# APP_1_Power_m.net
KiCad netlist of a schematic drawn in Altium Designer
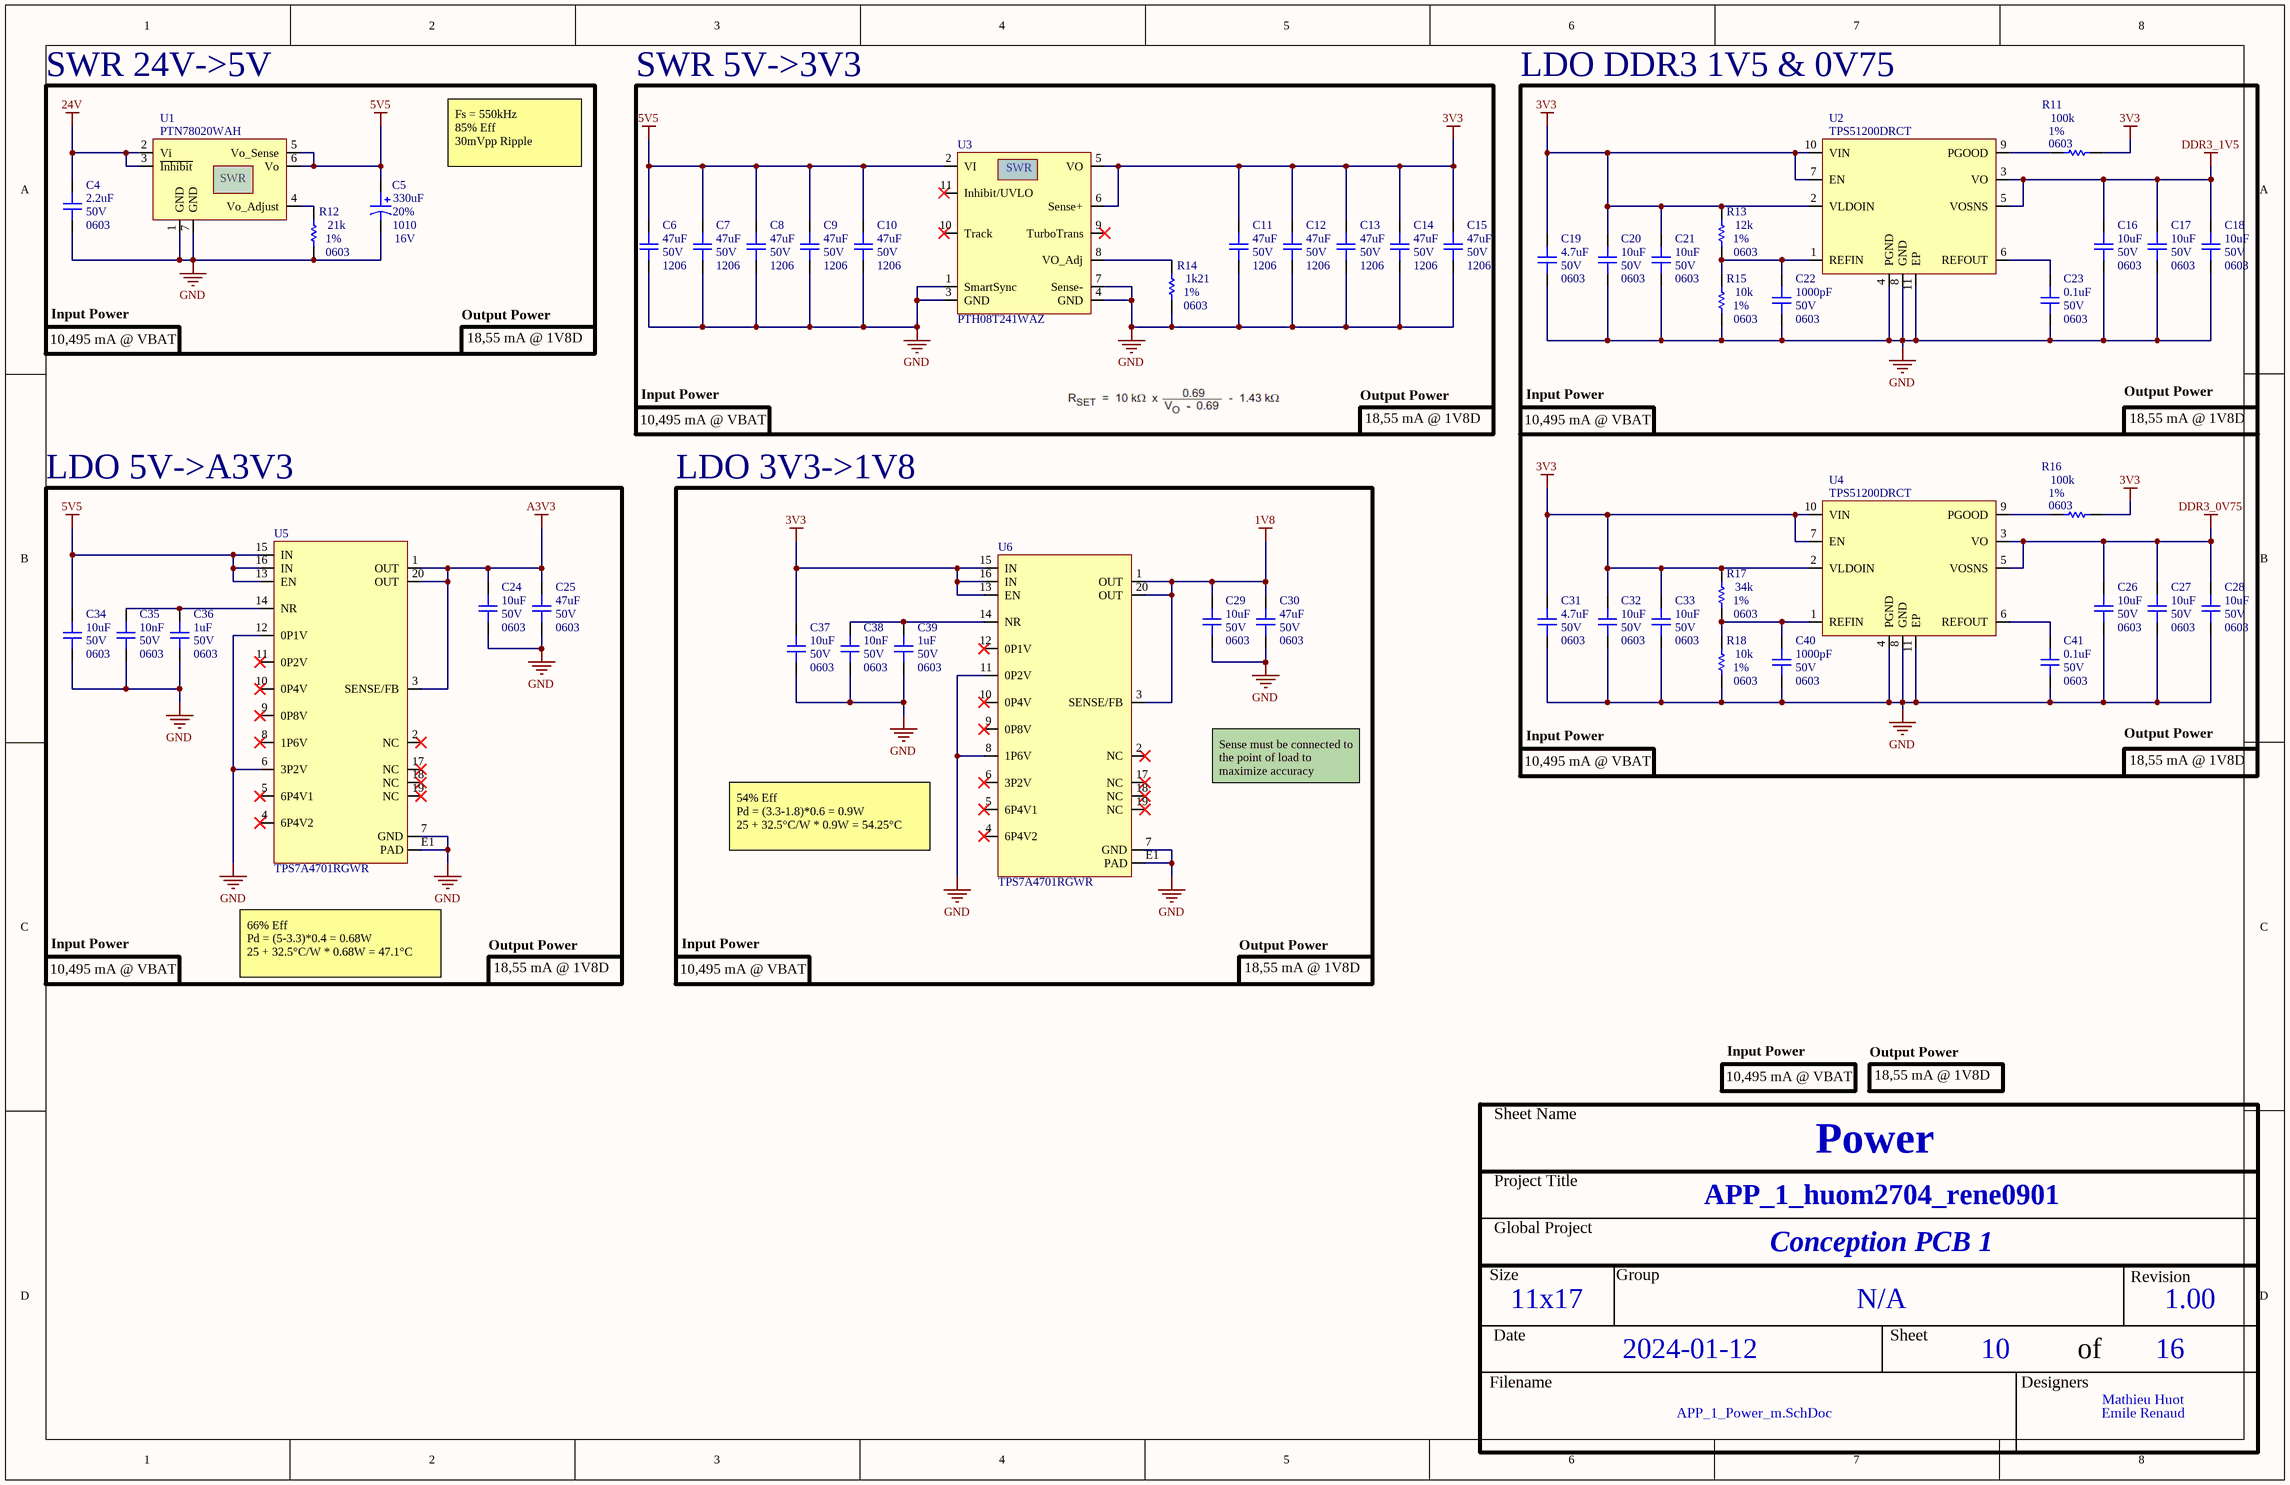
[diagram p0: APP_1_Power_m.SchDoc]

(export (version "E")
  (design (tool "Eeschema 10.0.6"))
  (components
    (comp (ref "C4")
      (value "2.2uF")
      (footprint "CAP_0603")
      (description "CAP - 0603")
      (fields
        (field (name "VOLTAGE") "50V")
        (field (name "PACKAGE") "0603")
        (field (name "CREATEDBY") "Jonathan Bouchard")
      )
      (libsource (lib "S7CAS_LIB2023") (part "CAP - 0603"))
    )
    (comp (ref "C5")
      (value "330uF")
      (footprint "CAP_ALU_1010_vishay")
      (description "CAP - ALU 330uF 20% 16V - 1010")
      (fields
        (field (name "MFG") "Vishay Dale")
        (field (name "MFG PART NUMBER") "MAL214699501E3")
        (field (name "VOLTAGE") "16V")
        (field (name "PACKAGE") "1010")
        (field (name "PRECISION") "20%")
        (field (name "CREATEDBY") "Jonathan Bouchard")
      )
      (libsource (lib "S7CAS_LIB2023") (part "CAP_ALU_MAL214699501E3"))
    )
    (comp (ref "C6")
      (value "47uF")
      (footprint "CAP_1206")
      (description "CAP - 1206")
      (fields
        (field (name "VOLTAGE") "50V")
        (field (name "PACKAGE") "1206")
        (field (name "CREATEDBY") "Jonathan Bouchard")
      )
      (libsource (lib "S7CAS_LIB2023") (part "CAP - 1206"))
    )
    (comp (ref "C7")
      (value "47uF")
      (footprint "CAP_1206")
      (description "CAP - 1206")
      (fields
        (field (name "VOLTAGE") "50V")
        (field (name "PACKAGE") "1206")
        (field (name "CREATEDBY") "Jonathan Bouchard")
      )
      (libsource (lib "S7CAS_LIB2023") (part "CAP - 1206"))
    )
    (comp (ref "C8")
      (value "47uF")
      (footprint "CAP_1206")
      (description "CAP - 1206")
      (fields
        (field (name "VOLTAGE") "50V")
        (field (name "PACKAGE") "1206")
        (field (name "CREATEDBY") "Jonathan Bouchard")
      )
      (libsource (lib "S7CAS_LIB2023") (part "CAP - 1206"))
    )
    (comp (ref "C9")
      (value "47uF")
      (footprint "CAP_1206")
      (description "CAP - 1206")
      (fields
        (field (name "VOLTAGE") "50V")
        (field (name "PACKAGE") "1206")
        (field (name "CREATEDBY") "Jonathan Bouchard")
      )
      (libsource (lib "S7CAS_LIB2023") (part "CAP - 1206"))
    )
    (comp (ref "C10")
      (value "47uF")
      (footprint "CAP_1206")
      (description "CAP - 1206")
      (fields
        (field (name "VOLTAGE") "50V")
        (field (name "PACKAGE") "1206")
        (field (name "CREATEDBY") "Jonathan Bouchard")
      )
      (libsource (lib "S7CAS_LIB2023") (part "CAP - 1206"))
    )
    (comp (ref "C11")
      (value "47uF")
      (footprint "CAP_1206")
      (description "CAP - 1206")
      (fields
        (field (name "VOLTAGE") "50V")
        (field (name "PACKAGE") "1206")
        (field (name "CREATEDBY") "Jonathan Bouchard")
      )
      (libsource (lib "S7CAS_LIB2023") (part "CAP - 1206"))
    )
    (comp (ref "C12")
      (value "47uF")
      (footprint "CAP_1206")
      (description "CAP - 1206")
      (fields
        (field (name "VOLTAGE") "50V")
        (field (name "PACKAGE") "1206")
        (field (name "CREATEDBY") "Jonathan Bouchard")
      )
      (libsource (lib "S7CAS_LIB2023") (part "CAP - 1206"))
    )
    (comp (ref "C13")
      (value "47uF")
      (footprint "CAP_1206")
      (description "CAP - 1206")
      (fields
        (field (name "VOLTAGE") "50V")
        (field (name "PACKAGE") "1206")
        (field (name "CREATEDBY") "Jonathan Bouchard")
      )
      (libsource (lib "S7CAS_LIB2023") (part "CAP - 1206"))
    )
    (comp (ref "C14")
      (value "47uF")
      (footprint "CAP_1206")
      (description "CAP - 1206")
      (fields
        (field (name "VOLTAGE") "50V")
        (field (name "PACKAGE") "1206")
        (field (name "CREATEDBY") "Jonathan Bouchard")
      )
      (libsource (lib "S7CAS_LIB2023") (part "CAP - 1206"))
    )
    (comp (ref "C15")
      (value "47uF")
      (footprint "CAP_1206")
      (description "CAP - 1206")
      (fields
        (field (name "VOLTAGE") "50V")
        (field (name "PACKAGE") "1206")
        (field (name "CREATEDBY") "Jonathan Bouchard")
      )
      (libsource (lib "S7CAS_LIB2023") (part "CAP - 1206"))
    )
    (comp (ref "C16")
      (value "10uF")
      (footprint "CAP_0603")
      (description "CAP - 0603")
      (fields
        (field (name "VOLTAGE") "50V")
        (field (name "PACKAGE") "0603")
        (field (name "CREATEDBY") "Jonathan Bouchard")
      )
      (libsource (lib "S7CAS_LIB2023") (part "CAP - 0603"))
    )
    (comp (ref "C17")
      (value "10uF")
      (footprint "CAP_0603")
      (description "CAP - 0603")
      (fields
        (field (name "VOLTAGE") "50V")
        (field (name "PACKAGE") "0603")
        (field (name "CREATEDBY") "Jonathan Bouchard")
      )
      (libsource (lib "S7CAS_LIB2023") (part "CAP - 0603"))
    )
    (comp (ref "C18")
      (value "10uF")
      (footprint "CAP_0603")
      (description "CAP - 0603")
      (fields
        (field (name "VOLTAGE") "50V")
        (field (name "PACKAGE") "0603")
        (field (name "CREATEDBY") "Jonathan Bouchard")
      )
      (libsource (lib "S7CAS_LIB2023") (part "CAP - 0603"))
    )
    (comp (ref "C19")
      (value "4.7uF")
      (footprint "CAP_0603")
      (description "CAP - 0603")
      (fields
        (field (name "VOLTAGE") "50V")
        (field (name "PACKAGE") "0603")
        (field (name "CREATEDBY") "Jonathan Bouchard")
      )
      (libsource (lib "S7CAS_LIB2023") (part "CAP - 0603"))
    )
    (comp (ref "C20")
      (value "10uF")
      (footprint "CAP_0603")
      (description "CAP - 0603")
      (fields
        (field (name "VOLTAGE") "50V")
        (field (name "PACKAGE") "0603")
        (field (name "CREATEDBY") "Jonathan Bouchard")
      )
      (libsource (lib "S7CAS_LIB2023") (part "CAP - 0603"))
    )
    (comp (ref "C21")
      (value "10uF")
      (footprint "CAP_0603")
      (description "CAP - 0603")
      (fields
        (field (name "VOLTAGE") "50V")
        (field (name "PACKAGE") "0603")
        (field (name "CREATEDBY") "Jonathan Bouchard")
      )
      (libsource (lib "S7CAS_LIB2023") (part "CAP - 0603"))
    )
    (comp (ref "C22")
      (value "1000pF")
      (footprint "CAP_0603")
      (description "CAP - 0603")
      (fields
        (field (name "VOLTAGE") "50V")
        (field (name "PACKAGE") "0603")
        (field (name "CREATEDBY") "Jonathan Bouchard")
      )
      (libsource (lib "S7CAS_LIB2023") (part "CAP - 0603"))
    )
    (comp (ref "C23")
      (value "0.1uF")
      (footprint "CAP_0603")
      (description "CAP - 0603")
      (fields
        (field (name "VOLTAGE") "50V")
        (field (name "PACKAGE") "0603")
        (field (name "CREATEDBY") "Jonathan Bouchard")
      )
      (libsource (lib "S7CAS_LIB2023") (part "CAP - 0603"))
    )
    (comp (ref "C24")
      (value "10uF")
      (footprint "CAP_0603")
      (description "CAP - 0603")
      (fields
        (field (name "VOLTAGE") "50V")
        (field (name "PACKAGE") "0603")
        (field (name "CREATEDBY") "Jonathan Bouchard")
      )
      (libsource (lib "S7CAS_LIB2023") (part "CAP - 0603"))
    )
    (comp (ref "C25")
      (value "47uF")
      (footprint "CAP_0603")
      (description "CAP - 0603")
      (fields
        (field (name "VOLTAGE") "50V")
        (field (name "PACKAGE") "0603")
        (field (name "CREATEDBY") "Jonathan Bouchard")
      )
      (libsource (lib "S7CAS_LIB2023") (part "CAP - 0603"))
    )
    (comp (ref "C26")
      (value "10uF")
      (footprint "CAP_0603")
      (description "CAP - 0603")
      (fields
        (field (name "VOLTAGE") "50V")
        (field (name "PACKAGE") "0603")
        (field (name "CREATEDBY") "Jonathan Bouchard")
      )
      (libsource (lib "S7CAS_LIB2023") (part "CAP - 0603"))
    )
    (comp (ref "C27")
      (value "10uF")
      (footprint "CAP_0603")
      (description "CAP - 0603")
      (fields
        (field (name "VOLTAGE") "50V")
        (field (name "PACKAGE") "0603")
        (field (name "CREATEDBY") "Jonathan Bouchard")
      )
      (libsource (lib "S7CAS_LIB2023") (part "CAP - 0603"))
    )
    (comp (ref "C28")
      (value "10uF")
      (footprint "CAP_0603")
      (description "CAP - 0603")
      (fields
        (field (name "VOLTAGE") "50V")
        (field (name "PACKAGE") "0603")
        (field (name "CREATEDBY") "Jonathan Bouchard")
      )
      (libsource (lib "S7CAS_LIB2023") (part "CAP - 0603"))
    )
    (comp (ref "C29")
      (value "10uF")
      (footprint "CAP_0603")
      (description "CAP - 0603")
      (fields
        (field (name "VOLTAGE") "50V")
        (field (name "PACKAGE") "0603")
        (field (name "CREATEDBY") "Jonathan Bouchard")
      )
      (libsource (lib "S7CAS_LIB2023") (part "CAP - 0603"))
    )
    (comp (ref "C30")
      (value "47uF")
      (footprint "CAP_0603")
      (description "CAP - 0603")
      (fields
        (field (name "VOLTAGE") "50V")
        (field (name "PACKAGE") "0603")
        (field (name "CREATEDBY") "Jonathan Bouchard")
      )
      (libsource (lib "S7CAS_LIB2023") (part "CAP - 0603"))
    )
    (comp (ref "C31")
      (value "4.7uF")
      (footprint "CAP_0603")
      (description "CAP - 0603")
      (fields
        (field (name "VOLTAGE") "50V")
        (field (name "PACKAGE") "0603")
        (field (name "CREATEDBY") "Jonathan Bouchard")
      )
      (libsource (lib "S7CAS_LIB2023") (part "CAP - 0603"))
    )
    (comp (ref "C32")
      (value "10uF")
      (footprint "CAP_0603")
      (description "CAP - 0603")
      (fields
        (field (name "VOLTAGE") "50V")
        (field (name "PACKAGE") "0603")
        (field (name "CREATEDBY") "Jonathan Bouchard")
      )
      (libsource (lib "S7CAS_LIB2023") (part "CAP - 0603"))
    )
    (comp (ref "C33")
      (value "10uF")
      (footprint "CAP_0603")
      (description "CAP - 0603")
      (fields
        (field (name "VOLTAGE") "50V")
        (field (name "PACKAGE") "0603")
        (field (name "CREATEDBY") "Jonathan Bouchard")
      )
      (libsource (lib "S7CAS_LIB2023") (part "CAP - 0603"))
    )
    (comp (ref "C34")
      (value "10uF")
      (footprint "CAP_0603")
      (description "CAP - 0603")
      (fields
        (field (name "VOLTAGE") "50V")
        (field (name "PACKAGE") "0603")
        (field (name "CREATEDBY") "Jonathan Bouchard")
      )
      (libsource (lib "S7CAS_LIB2023") (part "CAP - 0603"))
    )
    (comp (ref "C35")
      (value "10nF")
      (footprint "CAP_0603")
      (description "CAP - 0603")
      (fields
        (field (name "VOLTAGE") "50V")
        (field (name "PACKAGE") "0603")
        (field (name "CREATEDBY") "Jonathan Bouchard")
      )
      (libsource (lib "S7CAS_LIB2023") (part "CAP - 0603"))
    )
    (comp (ref "C36")
      (value "1uF")
      (footprint "CAP_0603")
      (description "CAP - 0603")
      (fields
        (field (name "VOLTAGE") "50V")
        (field (name "PACKAGE") "0603")
        (field (name "CREATEDBY") "Jonathan Bouchard")
      )
      (libsource (lib "S7CAS_LIB2023") (part "CAP - 0603"))
    )
    (comp (ref "C37")
      (value "10uF")
      (footprint "CAP_0603")
      (description "CAP - 0603")
      (fields
        (field (name "VOLTAGE") "50V")
        (field (name "PACKAGE") "0603")
        (field (name "CREATEDBY") "Jonathan Bouchard")
      )
      (libsource (lib "S7CAS_LIB2023") (part "CAP - 0603"))
    )
    (comp (ref "C38")
      (value "10nF")
      (footprint "CAP_0603")
      (description "CAP - 0603")
      (fields
        (field (name "VOLTAGE") "50V")
        (field (name "PACKAGE") "0603")
        (field (name "CREATEDBY") "Jonathan Bouchard")
      )
      (libsource (lib "S7CAS_LIB2023") (part "CAP - 0603"))
    )
    (comp (ref "C39")
      (value "1uF")
      (footprint "CAP_0603")
      (description "CAP - 0603")
      (fields
        (field (name "VOLTAGE") "50V")
        (field (name "PACKAGE") "0603")
        (field (name "CREATEDBY") "Jonathan Bouchard")
      )
      (libsource (lib "S7CAS_LIB2023") (part "CAP - 0603"))
    )
    (comp (ref "C40")
      (value "1000pF")
      (footprint "CAP_0603")
      (description "CAP - 0603")
      (fields
        (field (name "VOLTAGE") "50V")
        (field (name "PACKAGE") "0603")
        (field (name "CREATEDBY") "Jonathan Bouchard")
      )
      (libsource (lib "S7CAS_LIB2023") (part "CAP - 0603"))
    )
    (comp (ref "C41")
      (value "0.1uF")
      (footprint "CAP_0603")
      (description "CAP - 0603")
      (fields
        (field (name "VOLTAGE") "50V")
        (field (name "PACKAGE") "0603")
        (field (name "CREATEDBY") "Jonathan Bouchard")
      )
      (libsource (lib "S7CAS_LIB2023") (part "CAP - 0603"))
    )
    (comp (ref "R11")
      (value "100k")
      (footprint "RES_0603")
      (description "RES - 0603")
      (fields
        (field (name "PACKAGE") "0603")
        (field (name "PRECISION") "1%")
        (field (name "CREATEDBY") "Jonathan Bouchard")
      )
      (libsource (lib "S7CAS_LIB2023") (part "RES - 0603"))
    )
    (comp (ref "R12")
      (value "21k")
      (footprint "RES_0603")
      (description "RES - 0603")
      (fields
        (field (name "PACKAGE") "0603")
        (field (name "PRECISION") "1%")
        (field (name "CREATEDBY") "Jonathan Bouchard")
      )
      (libsource (lib "S7CAS_LIB2023") (part "RES - 0603"))
    )
    (comp (ref "R13")
      (value "12k")
      (footprint "RES_0603")
      (description "RES - 0603")
      (fields
        (field (name "PACKAGE") "0603")
        (field (name "PRECISION") "1%")
        (field (name "CREATEDBY") "Jonathan Bouchard")
      )
      (libsource (lib "S7CAS_LIB2023") (part "RES - 0603"))
    )
    (comp (ref "R14")
      (value "1k21")
      (footprint "RES_0603")
      (description "RES - 0603")
      (fields
        (field (name "PACKAGE") "0603")
        (field (name "PRECISION") "1%")
        (field (name "CREATEDBY") "Jonathan Bouchard")
      )
      (libsource (lib "S7CAS_LIB2023") (part "RES - 0603"))
    )
    (comp (ref "R15")
      (value "10k")
      (footprint "RES_0603")
      (description "RES - 0603")
      (fields
        (field (name "PACKAGE") "0603")
        (field (name "PRECISION") "1%")
        (field (name "CREATEDBY") "Jonathan Bouchard")
      )
      (libsource (lib "S7CAS_LIB2023") (part "RES - 0603"))
    )
    (comp (ref "R16")
      (value "100k")
      (footprint "RES_0603")
      (description "RES - 0603")
      (fields
        (field (name "PACKAGE") "0603")
        (field (name "PRECISION") "1%")
        (field (name "CREATEDBY") "Jonathan Bouchard")
      )
      (libsource (lib "S7CAS_LIB2023") (part "RES - 0603"))
    )
    (comp (ref "R17")
      (value "34k")
      (footprint "RES_0603")
      (description "RES - 0603")
      (fields
        (field (name "PACKAGE") "0603")
        (field (name "PRECISION") "1%")
        (field (name "CREATEDBY") "Jonathan Bouchard")
      )
      (libsource (lib "S7CAS_LIB2023") (part "RES - 0603"))
    )
    (comp (ref "R18")
      (value "10k")
      (footprint "RES_0603")
      (description "RES - 0603")
      (fields
        (field (name "PACKAGE") "0603")
        (field (name "PRECISION") "1%")
        (field (name "CREATEDBY") "Jonathan Bouchard")
      )
      (libsource (lib "S7CAS_LIB2023") (part "RES - 0603"))
    )
    (comp (ref "U1")
      (value "PTN78020WAH")
      (footprint "REG_SWR_PTN78020WAH")
      (description "REG - DC DC CONVERTER 2.5-12.6V 6A - TH")
      (fields
        (field (name "CREATEDBY/DATE") "Arnaud_Samson_2019-07-09")
        (field (name "VERIFIEDBY") "c.Paulin - 15 juillet 2019")
      )
      (libsource (lib "S7CAS_LIB2023") (part "REG_SWR_PTN78020WAH"))
    )
    (comp (ref "U2")
      (value "TPS51200DRCT")
      (footprint "REG_PMIC_TPS51200DRCT")
      (description "REG - DDR TERMINATION/REF REG - 10-VFDFN")
      (fields
        (field (name "CREATEDBY/DATE") "Joel Lemay 2019-03-19")
        (field (name "VERIFIEDBY") "Nicolas V. (2019-05-31)")
      )
      (libsource (lib "S7CAS_LIB2023") (part "REG_PMIC_TPS51200DRCT"))
    )
    (comp (ref "U3")
      (value "PTH08T241WAZ")
      (footprint "REG_SWR_PTH08T241WAZ")
      (description "REG - MODULE PIP 10A 14VIN - 11-SMD")
      (fields
        (field (name "CREATEDBY/DATE") "Olivier Bernard / 6/5/2018")
        (field (name "VERIFIEDBY") "Caroline Paulin / 10 juillet 2018")
      )
      (libsource (lib "S7CAS_LIB2023") (part "REG_SWR_PTH08T241WAZ"))
    )
    (comp (ref "U4")
      (value "TPS51200DRCT")
      (footprint "REG_PMIC_TPS51200DRCT")
      (description "REG - DDR TERMINATION/REF REG - 10-VFDFN")
      (fields
        (field (name "CREATEDBY/DATE") "Joel Lemay 2019-03-19")
        (field (name "VERIFIEDBY") "Nicolas V. (2019-05-31)")
      )
      (libsource (lib "S7CAS_LIB2023") (part "REG_PMIC_TPS51200DRCT"))
    )
    (comp (ref "U5")
      (value "TPS7A4701RGWR")
      (footprint "REG_TPS7A4701RGWR")
      (description "REG - LINEAR POS ADJ 1A - 20VQFN")
      (fields
        (field (name "CREATEDBY/DATE") "L-P Gauthier / 2018-05-29")
        (field (name "VERIFIEDBY") "Caroline Paulin - 28 sept 2018")
      )
      (libsource (lib "S7CAS_LIB2023") (part "REG_LDO_TPS7A4701RGWR"))
    )
    (comp (ref "U6")
      (value "TPS7A4701RGWR")
      (footprint "REG_TPS7A4701RGWR")
      (description "REG - LINEAR POS ADJ 1A - 20VQFN")
      (fields
        (field (name "CREATEDBY/DATE") "L-P Gauthier / 2018-05-29")
        (field (name "VERIFIEDBY") "Caroline Paulin - 28 sept 2018")
      )
      (libsource (lib "S7CAS_LIB2023") (part "REG_LDO_TPS7A4701RGWR"))
    )
  )
  (nets
    (net (code "1") (name "1V8") (class "Default")
      (node (ref "C29") (pin "2") (pinfunction "2_2") (pintype "passive"))
      (node (ref "C30") (pin "2") (pinfunction "2_2") (pintype "passive"))
      (node (ref "U6") (pin "1") (pinfunction "OUT_1") (pintype "passive"))
      (node (ref "U6") (pin "20") (pinfunction "OUT_20") (pintype "passive"))
      (node (ref "U6") (pin "3") (pinfunction "SENSE/FB_3") (pintype "passive"))
    )
    (net (code "2") (name "3V3") (class "Default")
      (node (ref "C11") (pin "2") (pinfunction "2_2") (pintype "passive"))
      (node (ref "C12") (pin "2") (pinfunction "2_2") (pintype "passive"))
      (node (ref "C13") (pin "2") (pinfunction "2_2") (pintype "passive"))
      (node (ref "C14") (pin "2") (pinfunction "2_2") (pintype "passive"))
      (node (ref "C15") (pin "2") (pinfunction "2_2") (pintype "passive"))
      (node (ref "C19") (pin "2") (pinfunction "2_2") (pintype "passive"))
      (node (ref "C20") (pin "2") (pinfunction "2_2") (pintype "passive"))
      (node (ref "C21") (pin "2") (pinfunction "2_2") (pintype "passive"))
      (node (ref "C31") (pin "2") (pinfunction "2_2") (pintype "passive"))
      (node (ref "C32") (pin "2") (pinfunction "2_2") (pintype "passive"))
      (node (ref "C33") (pin "2") (pinfunction "2_2") (pintype "passive"))
      (node (ref "C37") (pin "2") (pinfunction "2_2") (pintype "passive"))
      (node (ref "R11") (pin "2") (pinfunction "2_2") (pintype "passive"))
      (node (ref "R13") (pin "2") (pinfunction "2_2") (pintype "passive"))
      (node (ref "R16") (pin "2") (pinfunction "2_2") (pintype "passive"))
      (node (ref "R17") (pin "2") (pinfunction "2_2") (pintype "passive"))
      (node (ref "U2") (pin "10") (pinfunction "VIN_10") (pintype "passive"))
      (node (ref "U2") (pin "2") (pinfunction "VLDOIN_2") (pintype "passive"))
      (node (ref "U2") (pin "7") (pinfunction "EN_7") (pintype "passive"))
      (node (ref "U3") (pin "5") (pinfunction "VO_5") (pintype "passive"))
      (node (ref "U3") (pin "6") (pinfunction "Sense+_6") (pintype "passive"))
      (node (ref "U4") (pin "10") (pinfunction "VIN_10") (pintype "passive"))
      (node (ref "U4") (pin "2") (pinfunction "VLDOIN_2") (pintype "passive"))
      (node (ref "U4") (pin "7") (pinfunction "EN_7") (pintype "passive"))
      (node (ref "U6") (pin "13") (pinfunction "EN_13") (pintype "passive"))
      (node (ref "U6") (pin "15") (pinfunction "IN_15") (pintype "passive"))
      (node (ref "U6") (pin "16") (pinfunction "IN_16") (pintype "passive"))
    )
    (net (code "3") (name "5V5") (class "Default")
      (node (ref "C10") (pin "2") (pinfunction "2_2") (pintype "passive"))
      (node (ref "C34") (pin "2") (pinfunction "2_2") (pintype "passive"))
      (node (ref "C5") (pin "1") (pinfunction "1_1") (pintype "passive"))
      (node (ref "C6") (pin "2") (pinfunction "2_2") (pintype "passive"))
      (node (ref "C7") (pin "2") (pinfunction "2_2") (pintype "passive"))
      (node (ref "C8") (pin "2") (pinfunction "2_2") (pintype "passive"))
      (node (ref "C9") (pin "2") (pinfunction "2_2") (pintype "passive"))
      (node (ref "U1") (pin "5") (pinfunction "Vo_Sense_5") (pintype "passive"))
      (node (ref "U1") (pin "6") (pinfunction "Vo_6") (pintype "passive"))
      (node (ref "U3") (pin "2") (pinfunction "VI_2") (pintype "passive"))
      (node (ref "U5") (pin "13") (pinfunction "EN_13") (pintype "passive"))
      (node (ref "U5") (pin "15") (pinfunction "IN_15") (pintype "passive"))
      (node (ref "U5") (pin "16") (pinfunction "IN_16") (pintype "passive"))
    )
    (net (code "4") (name "24V") (class "Default")
      (node (ref "C4") (pin "2") (pinfunction "2_2") (pintype "passive"))
      (node (ref "U1") (pin "2") (pinfunction "Vi_2") (pintype "passive"))
      (node (ref "U1") (pin "3") (pinfunction "Inhibit_3") (pintype "passive"))
    )
    (net (code "5") (name "A3V3") (class "Default")
      (node (ref "C24") (pin "2") (pinfunction "2_2") (pintype "passive"))
      (node (ref "C25") (pin "2") (pinfunction "2_2") (pintype "passive"))
      (node (ref "U5") (pin "1") (pinfunction "OUT_1") (pintype "passive"))
      (node (ref "U5") (pin "20") (pinfunction "OUT_20") (pintype "passive"))
      (node (ref "U5") (pin "3") (pinfunction "SENSE/FB_3") (pintype "passive"))
    )
    (net (code "6") (name "DDR3_0V75") (class "Default")
      (node (ref "C26") (pin "2") (pinfunction "2_2") (pintype "passive"))
      (node (ref "C27") (pin "2") (pinfunction "2_2") (pintype "passive"))
      (node (ref "C28") (pin "2") (pinfunction "2_2") (pintype "passive"))
      (node (ref "U4") (pin "3") (pinfunction "VO_3") (pintype "passive"))
      (node (ref "U4") (pin "5") (pinfunction "VOSNS_5") (pintype "passive"))
    )
    (net (code "7") (name "DDR3_1V5") (class "Default")
      (node (ref "C16") (pin "2") (pinfunction "2_2") (pintype "passive"))
      (node (ref "C17") (pin "2") (pinfunction "2_2") (pintype "passive"))
      (node (ref "C18") (pin "2") (pinfunction "2_2") (pintype "passive"))
      (node (ref "U2") (pin "3") (pinfunction "VO_3") (pintype "passive"))
      (node (ref "U2") (pin "5") (pinfunction "VOSNS_5") (pintype "passive"))
    )
    (net (code "8") (name "GND") (class "Default")
      (node (ref "C10") (pin "1") (pinfunction "1_1") (pintype "passive"))
      (node (ref "C11") (pin "1") (pinfunction "1_1") (pintype "passive"))
      (node (ref "C12") (pin "1") (pinfunction "1_1") (pintype "passive"))
      (node (ref "C13") (pin "1") (pinfunction "1_1") (pintype "passive"))
      (node (ref "C14") (pin "1") (pinfunction "1_1") (pintype "passive"))
      (node (ref "C15") (pin "1") (pinfunction "1_1") (pintype "passive"))
      (node (ref "C16") (pin "1") (pinfunction "1_1") (pintype "passive"))
      (node (ref "C17") (pin "1") (pinfunction "1_1") (pintype "passive"))
      (node (ref "C18") (pin "1") (pinfunction "1_1") (pintype "passive"))
      (node (ref "C19") (pin "1") (pinfunction "1_1") (pintype "passive"))
      (node (ref "C20") (pin "1") (pinfunction "1_1") (pintype "passive"))
      (node (ref "C21") (pin "1") (pinfunction "1_1") (pintype "passive"))
      (node (ref "C22") (pin "1") (pinfunction "1_1") (pintype "passive"))
      (node (ref "C23") (pin "1") (pinfunction "1_1") (pintype "passive"))
      (node (ref "C24") (pin "1") (pinfunction "1_1") (pintype "passive"))
      (node (ref "C25") (pin "1") (pinfunction "1_1") (pintype "passive"))
      (node (ref "C26") (pin "1") (pinfunction "1_1") (pintype "passive"))
      (node (ref "C27") (pin "1") (pinfunction "1_1") (pintype "passive"))
      (node (ref "C28") (pin "1") (pinfunction "1_1") (pintype "passive"))
      (node (ref "C29") (pin "1") (pinfunction "1_1") (pintype "passive"))
      (node (ref "C30") (pin "1") (pinfunction "1_1") (pintype "passive"))
      (node (ref "C31") (pin "1") (pinfunction "1_1") (pintype "passive"))
      (node (ref "C32") (pin "1") (pinfunction "1_1") (pintype "passive"))
      (node (ref "C33") (pin "1") (pinfunction "1_1") (pintype "passive"))
      (node (ref "C34") (pin "1") (pinfunction "1_1") (pintype "passive"))
      (node (ref "C35") (pin "1") (pinfunction "1_1") (pintype "passive"))
      (node (ref "C36") (pin "1") (pinfunction "1_1") (pintype "passive"))
      (node (ref "C37") (pin "1") (pinfunction "1_1") (pintype "passive"))
      (node (ref "C38") (pin "1") (pinfunction "1_1") (pintype "passive"))
      (node (ref "C39") (pin "1") (pinfunction "1_1") (pintype "passive"))
      (node (ref "C4") (pin "1") (pinfunction "1_1") (pintype "passive"))
      (node (ref "C40") (pin "1") (pinfunction "1_1") (pintype "passive"))
      (node (ref "C41") (pin "1") (pinfunction "1_1") (pintype "passive"))
      (node (ref "C5") (pin "2") (pinfunction "2_2") (pintype "passive"))
      (node (ref "C6") (pin "1") (pinfunction "1_1") (pintype "passive"))
      (node (ref "C7") (pin "1") (pinfunction "1_1") (pintype "passive"))
      (node (ref "C8") (pin "1") (pinfunction "1_1") (pintype "passive"))
      (node (ref "C9") (pin "1") (pinfunction "1_1") (pintype "passive"))
      (node (ref "R12") (pin "1") (pinfunction "1_1") (pintype "passive"))
      (node (ref "R14") (pin "1") (pinfunction "1_1") (pintype "passive"))
      (node (ref "R15") (pin "1") (pinfunction "1_1") (pintype "passive"))
      (node (ref "R18") (pin "1") (pinfunction "1_1") (pintype "passive"))
      (node (ref "U1") (pin "1") (pinfunction "GND_1") (pintype "passive"))
      (node (ref "U1") (pin "7") (pinfunction "GND_7") (pintype "passive"))
      (node (ref "U2") (pin "11") (pinfunction "EP_11") (pintype "passive"))
      (node (ref "U2") (pin "4") (pinfunction "PGND_4") (pintype "passive"))
      (node (ref "U2") (pin "8") (pinfunction "GND_8") (pintype "passive"))
      (node (ref "U3") (pin "1") (pinfunction "SmartSync_1") (pintype "passive"))
      (node (ref "U3") (pin "3") (pinfunction "GND_3") (pintype "passive"))
      (node (ref "U3") (pin "4") (pinfunction "GND_4") (pintype "passive"))
      (node (ref "U3") (pin "7") (pinfunction "Sense-_7") (pintype "passive"))
      (node (ref "U4") (pin "11") (pinfunction "EP_11") (pintype "passive"))
      (node (ref "U4") (pin "4") (pinfunction "PGND_4") (pintype "passive"))
      (node (ref "U4") (pin "8") (pinfunction "GND_8") (pintype "passive"))
      (node (ref "U5") (pin "12") (pinfunction "0P1V_12") (pintype "passive"))
      (node (ref "U5") (pin "6") (pinfunction "3P2V_6") (pintype "passive"))
      (node (ref "U5") (pin "7") (pinfunction "GND_7") (pintype "passive"))
      (node (ref "U5") (pin "E1") (pinfunction "PAD_E1") (pintype "passive"))
      (node (ref "U6") (pin "11") (pinfunction "0P2V_11") (pintype "passive"))
      (node (ref "U6") (pin "7") (pinfunction "GND_7") (pintype "passive"))
      (node (ref "U6") (pin "8") (pinfunction "1P6V_8") (pintype "passive"))
      (node (ref "U6") (pin "E1") (pinfunction "PAD_E1") (pintype "passive"))
    )
    (net (code "9") (name "Net-(U1-Vo_Adjust)") (class "Default")
      (node (ref "R12") (pin "2") (pinfunction "2_2") (pintype "passive"))
      (node (ref "U1") (pin "4") (pinfunction "Vo_Adjust_4") (pintype "passive"))
    )
    (net (code "10") (name "Net-(U2-PGOOD)") (class "Default")
      (node (ref "R11") (pin "1") (pinfunction "1_1") (pintype "passive"))
      (node (ref "U2") (pin "9") (pinfunction "PGOOD_9") (pintype "passive"))
    )
    (net (code "11") (name "Net-(U2-REFIN)") (class "Default")
      (node (ref "C22") (pin "2") (pinfunction "2_2") (pintype "passive"))
      (node (ref "R13") (pin "1") (pinfunction "1_1") (pintype "passive"))
      (node (ref "R15") (pin "2") (pinfunction "2_2") (pintype "passive"))
      (node (ref "U2") (pin "1") (pinfunction "REFIN_1") (pintype "passive"))
    )
    (net (code "12") (name "Net-(U2-REFOUT)") (class "Default")
      (node (ref "C23") (pin "2") (pinfunction "2_2") (pintype "passive"))
      (node (ref "U2") (pin "6") (pinfunction "REFOUT_6") (pintype "passive"))
    )
    (net (code "13") (name "Net-(U3-VO_Adj)") (class "Default")
      (node (ref "R14") (pin "2") (pinfunction "2_2") (pintype "passive"))
      (node (ref "U3") (pin "8") (pinfunction "VO_Adj_8") (pintype "passive"))
    )
    (net (code "14") (name "Net-(U4-PGOOD)") (class "Default")
      (node (ref "R16") (pin "1") (pinfunction "1_1") (pintype "passive"))
      (node (ref "U4") (pin "9") (pinfunction "PGOOD_9") (pintype "passive"))
    )
    (net (code "15") (name "Net-(U4-REFIN)") (class "Default")
      (node (ref "C40") (pin "2") (pinfunction "2_2") (pintype "passive"))
      (node (ref "R17") (pin "1") (pinfunction "1_1") (pintype "passive"))
      (node (ref "R18") (pin "2") (pinfunction "2_2") (pintype "passive"))
      (node (ref "U4") (pin "1") (pinfunction "REFIN_1") (pintype "passive"))
    )
    (net (code "16") (name "Net-(U4-REFOUT)") (class "Default")
      (node (ref "C41") (pin "2") (pinfunction "2_2") (pintype "passive"))
      (node (ref "U4") (pin "6") (pinfunction "REFOUT_6") (pintype "passive"))
    )
    (net (code "17") (name "Net-(U5-NR)") (class "Default")
      (node (ref "C35") (pin "2") (pinfunction "2_2") (pintype "passive"))
      (node (ref "C36") (pin "2") (pinfunction "2_2") (pintype "passive"))
      (node (ref "U5") (pin "14") (pinfunction "NR_14") (pintype "passive"))
    )
    (net (code "18") (name "Net-(U6-NR)") (class "Default")
      (node (ref "C38") (pin "2") (pinfunction "2_2") (pintype "passive"))
      (node (ref "C39") (pin "2") (pinfunction "2_2") (pintype "passive"))
      (node (ref "U6") (pin "14") (pinfunction "NR_14") (pintype "passive"))
    )
    (net (code "19") (name "unconnected-(U3-Inhibit{slash}UVLO-Pad11)") (class "Default")
      (node (ref "U3") (pin "11") (pinfunction "Inhibit/UVLO_11") (pintype "passive+no_connect"))
    )
    (net (code "20") (name "unconnected-(U3-Track-Pad10)") (class "Default")
      (node (ref "U3") (pin "10") (pinfunction "Track_10") (pintype "passive+no_connect"))
    )
    (net (code "21") (name "unconnected-(U3-TurboTrans-Pad9)") (class "Default")
      (node (ref "U3") (pin "9") (pinfunction "TurboTrans_9") (pintype "passive+no_connect"))
    )
    (net (code "22") (name "unconnected-(U5-0P2V-Pad11)") (class "Default")
      (node (ref "U5") (pin "11") (pinfunction "0P2V_11") (pintype "passive+no_connect"))
    )
    (net (code "23") (name "unconnected-(U5-0P4V-Pad10)") (class "Default")
      (node (ref "U5") (pin "10") (pinfunction "0P4V_10") (pintype "passive+no_connect"))
    )
    (net (code "24") (name "unconnected-(U5-0P8V-Pad9)") (class "Default")
      (node (ref "U5") (pin "9") (pinfunction "0P8V_9") (pintype "passive+no_connect"))
    )
    (net (code "25") (name "unconnected-(U5-1P6V-Pad8)") (class "Default")
      (node (ref "U5") (pin "8") (pinfunction "1P6V_8") (pintype "passive+no_connect"))
    )
    (net (code "26") (name "unconnected-(U5-6P4V1-Pad5)") (class "Default")
      (node (ref "U5") (pin "5") (pinfunction "6P4V1_5") (pintype "passive+no_connect"))
    )
    (net (code "27") (name "unconnected-(U5-6P4V2-Pad4)") (class "Default")
      (node (ref "U5") (pin "4") (pinfunction "6P4V2_4") (pintype "passive+no_connect"))
    )
    (net (code "28") (name "unconnected-(U5-NC-Pad2)") (class "Default")
      (node (ref "U5") (pin "2") (pinfunction "NC_2") (pintype "passive+no_connect"))
    )
    (net (code "29") (name "unconnected-(U5-NC-Pad17)") (class "Default")
      (node (ref "U5") (pin "17") (pinfunction "NC_17") (pintype "passive+no_connect"))
    )
    (net (code "30") (name "unconnected-(U5-NC-Pad18)") (class "Default")
      (node (ref "U5") (pin "18") (pinfunction "NC_18") (pintype "passive+no_connect"))
    )
    (net (code "31") (name "unconnected-(U5-NC-Pad19)") (class "Default")
      (node (ref "U5") (pin "19") (pinfunction "NC_19") (pintype "passive+no_connect"))
    )
    (net (code "32") (name "unconnected-(U6-0P1V-Pad12)") (class "Default")
      (node (ref "U6") (pin "12") (pinfunction "0P1V_12") (pintype "passive+no_connect"))
    )
    (net (code "33") (name "unconnected-(U6-0P4V-Pad10)") (class "Default")
      (node (ref "U6") (pin "10") (pinfunction "0P4V_10") (pintype "passive+no_connect"))
    )
    (net (code "34") (name "unconnected-(U6-0P8V-Pad9)") (class "Default")
      (node (ref "U6") (pin "9") (pinfunction "0P8V_9") (pintype "passive+no_connect"))
    )
    (net (code "35") (name "unconnected-(U6-3P2V-Pad6)") (class "Default")
      (node (ref "U6") (pin "6") (pinfunction "3P2V_6") (pintype "passive+no_connect"))
    )
    (net (code "36") (name "unconnected-(U6-6P4V1-Pad5)") (class "Default")
      (node (ref "U6") (pin "5") (pinfunction "6P4V1_5") (pintype "passive+no_connect"))
    )
    (net (code "37") (name "unconnected-(U6-6P4V2-Pad4)") (class "Default")
      (node (ref "U6") (pin "4") (pinfunction "6P4V2_4") (pintype "passive+no_connect"))
    )
    (net (code "38") (name "unconnected-(U6-NC-Pad2)") (class "Default")
      (node (ref "U6") (pin "2") (pinfunction "NC_2") (pintype "passive+no_connect"))
    )
    (net (code "39") (name "unconnected-(U6-NC-Pad17)") (class "Default")
      (node (ref "U6") (pin "17") (pinfunction "NC_17") (pintype "passive+no_connect"))
    )
    (net (code "40") (name "unconnected-(U6-NC-Pad18)") (class "Default")
      (node (ref "U6") (pin "18") (pinfunction "NC_18") (pintype "passive+no_connect"))
    )
    (net (code "41") (name "unconnected-(U6-NC-Pad19)") (class "Default")
      (node (ref "U6") (pin "19") (pinfunction "NC_19") (pintype "passive+no_connect"))
    )
  )
)
